# SCH_ReTOoric_2025-10-21.net
KiCad netlist of a schematic drawn in EasyEDA
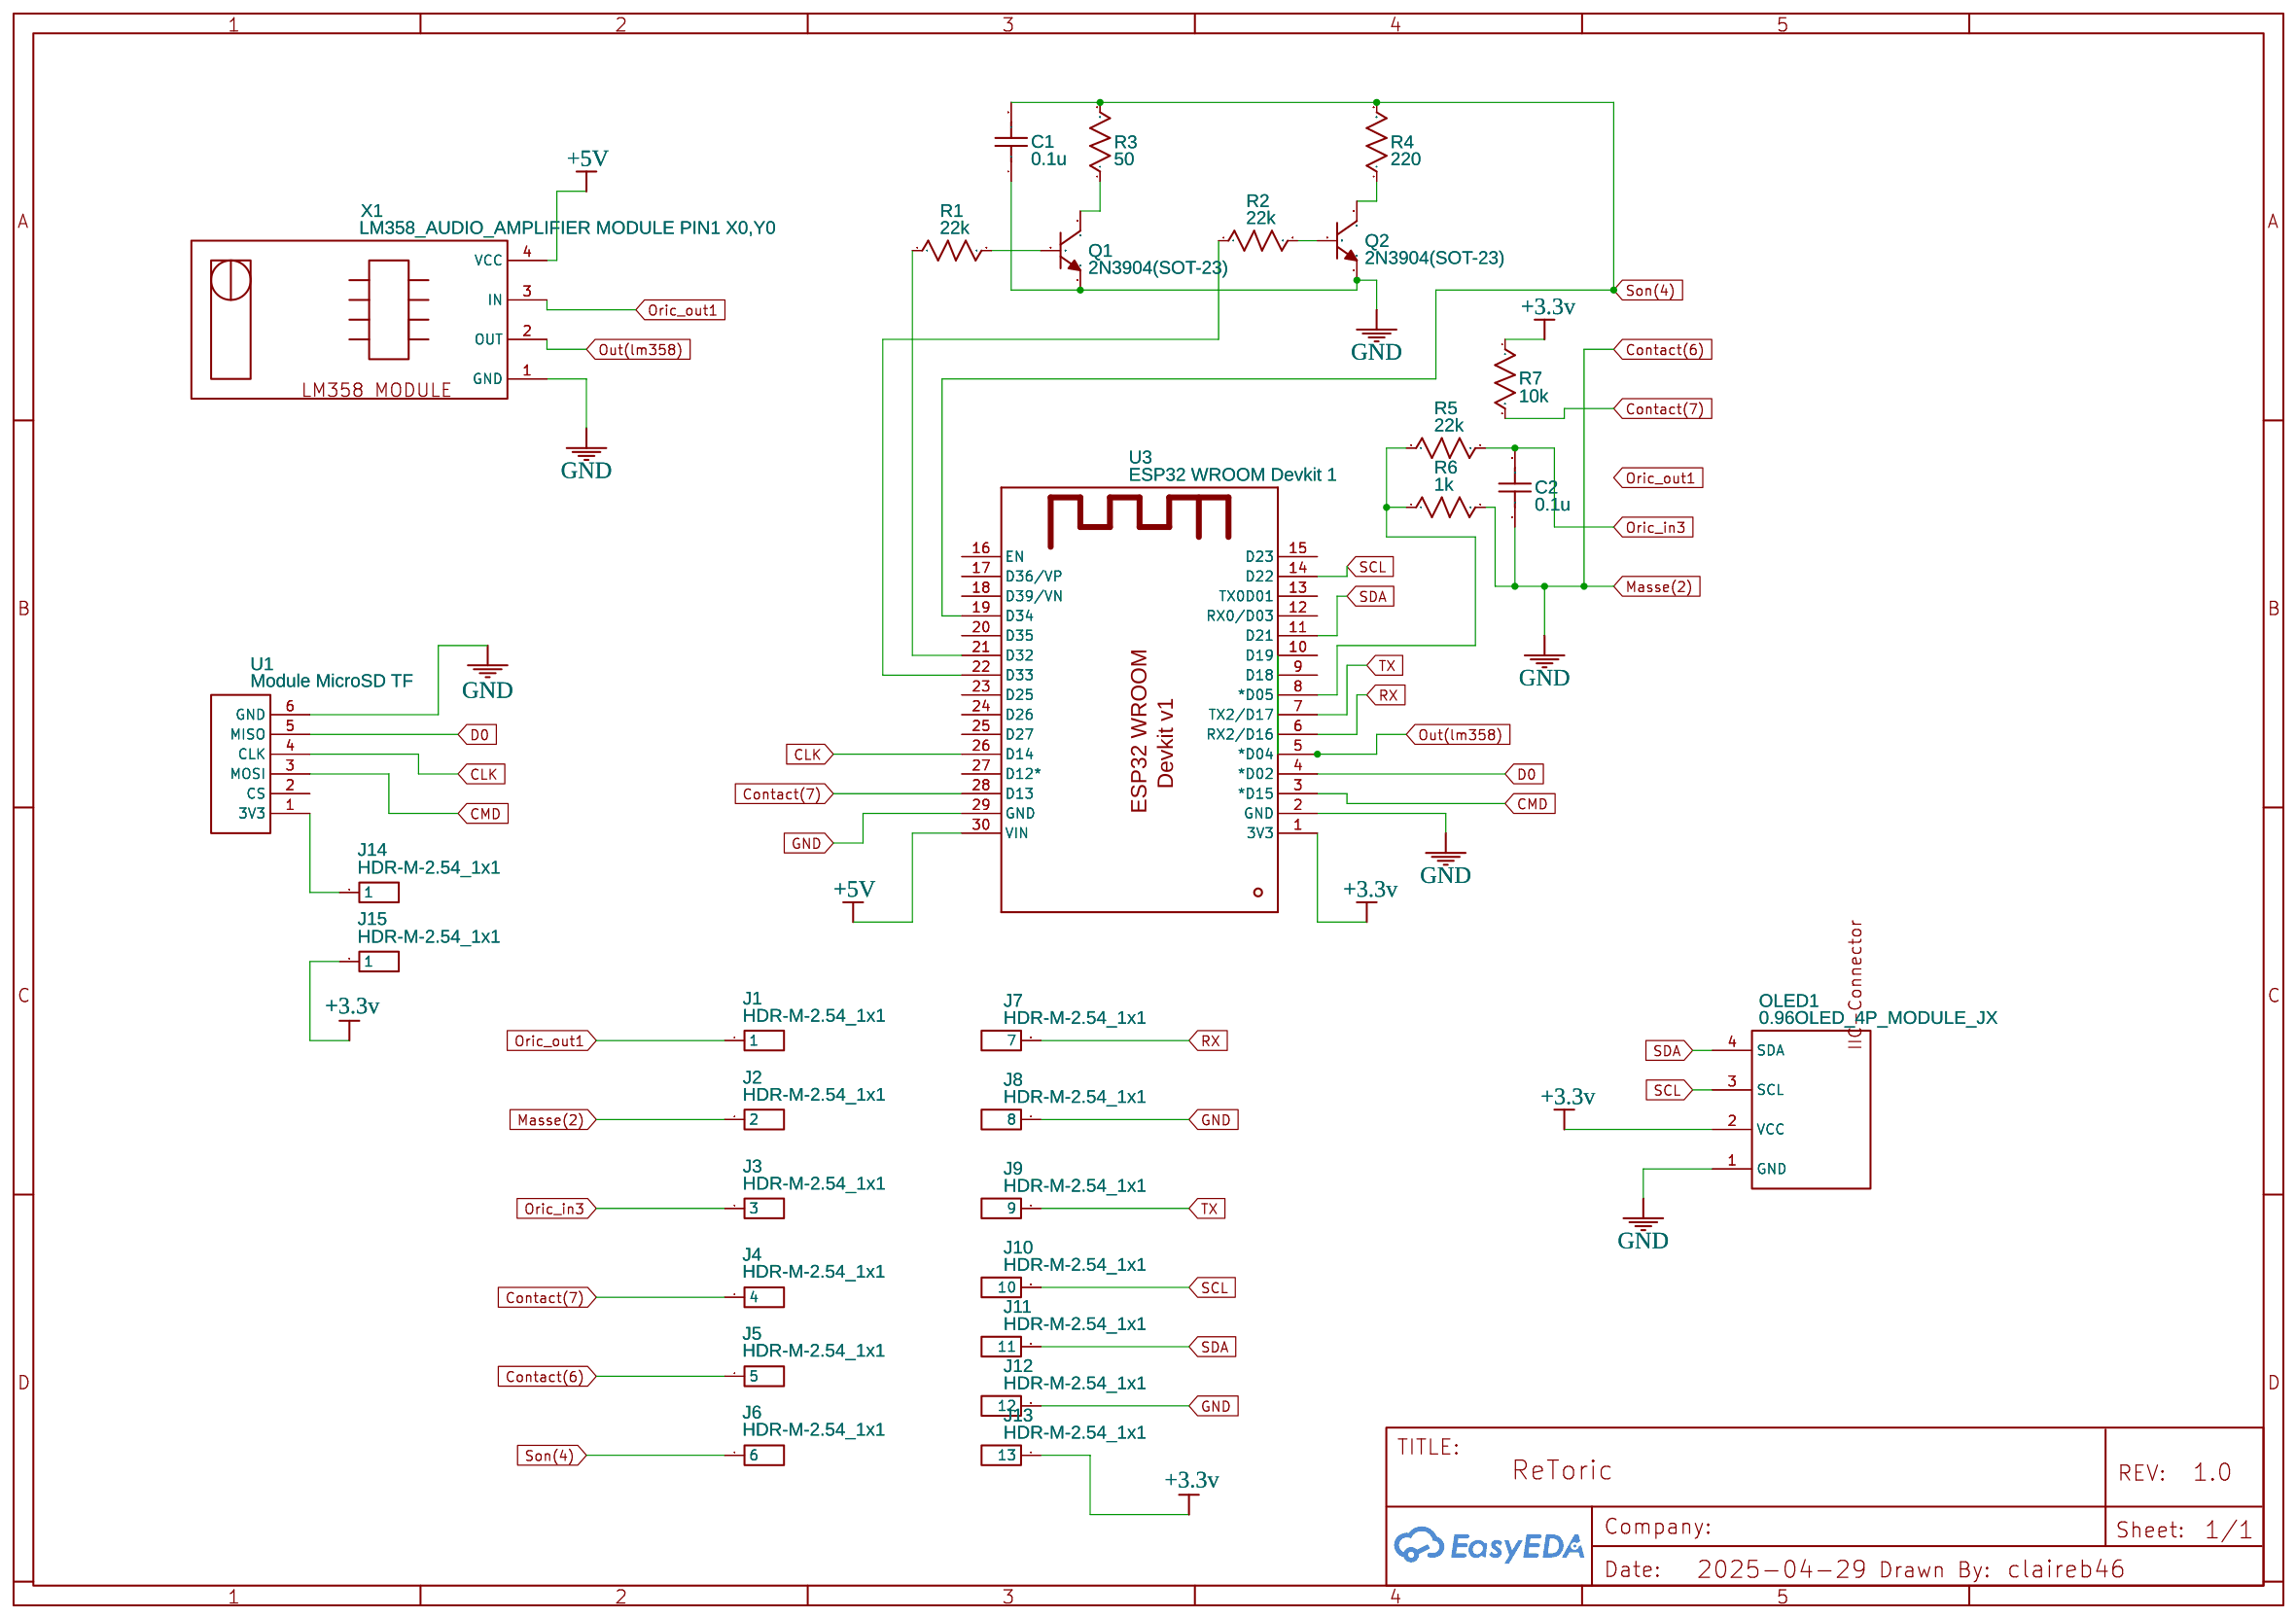
[diagram p0: schematic sheet]

(export (version "E")
  (design (tool "Eeschema 10.0.6"))
  (components
    (comp (ref "C1") (value "0.1u") (libsource (lib "") (part "C_0603_US")))
    (comp (ref "C2") (value "0.1u") (libsource (lib "") (part "C_0603_US")))
    (comp (ref "J1") (value "HDR-M-2.54_1x1") (libsource (lib "") (part "HDR-M-2.54_1x1")))
    (comp (ref "J2") (value "HDR-M-2.54_1x1") (libsource (lib "") (part "HDR-M-2.54_1x1_3")))
    (comp (ref "J3") (value "HDR-M-2.54_1x1") (libsource (lib "") (part "HDR-M-2.54_1x1_2")))
    (comp (ref "J4") (value "HDR-M-2.54_1x1") (libsource (lib "") (part "HDR-M-2.54_1x1_11")))
    (comp (ref "J5") (value "HDR-M-2.54_1x1") (libsource (lib "") (part "HDR-M-2.54_1x1_1")))
    (comp (ref "J6") (value "HDR-M-2.54_1x1") (libsource (lib "") (part "HDR-M-2.54_1x1_7")))
    (comp (ref "J7") (value "HDR-M-2.54_1x1") (libsource (lib "") (part "HDR-M-2.54_1x1_12")))
    (comp (ref "J8") (value "HDR-M-2.54_1x1") (libsource (lib "") (part "HDR-M-2.54_1x1_8")))
    (comp (ref "J9") (value "HDR-M-2.54_1x1") (libsource (lib "") (part "HDR-M-2.54_1x1_9")))
    (comp (ref "J10") (value "HDR-M-2.54_1x1") (libsource (lib "") (part "HDR-M-2.54_1x1_5")))
    (comp (ref "J11") (value "HDR-M-2.54_1x1") (libsource (lib "") (part "HDR-M-2.54_1x1_4")))
    (comp (ref "J12") (value "HDR-M-2.54_1x1") (libsource (lib "") (part "HDR-M-2.54_1x1_10")))
    (comp (ref "J13") (value "HDR-M-2.54_1x1") (libsource (lib "") (part "HDR-M-2.54_1x1_6")))
    (comp (ref "J14") (value "HDR-M-2.54_1x1") (libsource (lib "") (part "HDR-M-2.54_1x1")))
    (comp (ref "J15") (value "HDR-M-2.54_1x1") (libsource (lib "") (part "HDR-M-2.54_1x1")))
    (comp (ref "OLED1") (value "0.96OLED_4P_MODULE_JX") (libsource (lib "") (part "0.96OLED_4P_MODULE_JX")))
    (comp (ref "Q1")
      (value "2N3904(SOT-23)")
      (fields (field (name "Manufacturer Part") "2n3904S-RTK/PS") (field (name "Manufacturer") "KEC"))
      (libsource (lib "") (part "2N3904(SOT-23)"))
    )
    (comp (ref "Q2")
      (value "2N3904(SOT-23)")
      (fields (field (name "Manufacturer Part") "2n3904S-RTK/PS") (field (name "Manufacturer") "KEC"))
      (libsource (lib "") (part "2N3904(SOT-23)"))
    )
    (comp (ref "R1") (value "22k") (libsource (lib "") (part "R_0603_US")))
    (comp (ref "R2") (value "22k") (libsource (lib "") (part "R_0603_US")))
    (comp (ref "R3") (value "50") (libsource (lib "") (part "R_0603_US_2")))
    (comp (ref "R4") (value "220") (libsource (lib "") (part "R_0603_US_2")))
    (comp (ref "R5") (value "22k") (libsource (lib "") (part "R_0603_US")))
    (comp (ref "R6") (value "1k") (libsource (lib "") (part "R_0603_US")))
    (comp (ref "R7") (value "10k") (libsource (lib "") (part "R_0603_US_1")))
    (comp (ref "U1")
      (value "Module MicroSD TF")
      (fields
        (field (name "Manufacturer Part") "TF Micro SD Card Module")
        (field (name "Manufacturer") "SZHAD Technology Store")
      )
      (libsource (lib "") (part "Module MicroSD TF"))
    )
    (comp (ref "U3")
      (value "ESP32 WROOM Devkit 1")
      (fields (field (name "Manufacturer") "Espresssif"))
      (libsource (lib "") (part "ESP32 WROOM Devkit 1"))
    )
    (comp (ref "X1")
      (value "LM358_AUDIO_AMPLIFIER MODULE PIN1 X0,Y0")
      (fields (field (name "Manufacturer Part") "4mm cable to pcb concector 2pins"))
      (libsource (lib "") (part "LM358_AUDIO_AMPLIFIER MODULE PIN1 X0,Y0"))
    )
  )
  (nets
    (net (code "1") (name "+3.3v") (class "Default")
      (node (ref "J13") (pin "1") (pinfunction "13_1") (pintype "input"))
      (node (ref "J15") (pin "1") (pinfunction "1_1") (pintype "input"))
      (node (ref "OLED1") (pin "2") (pinfunction "VCC_2") (pintype "unspecified"))
      (node (ref "R7") (pin "1") (pinfunction "1_1") (pintype "unspecified"))
      (node (ref "U3") (pin "1") (pinfunction "3V3_1") (pintype "passive"))
    )
    (net (code "2") (name "+5V") (class "Default")
      (node (ref "U3") (pin "30") (pinfunction "VIN_30") (pintype "passive"))
      (node (ref "X1") (pin "4") (pinfunction "VCC_4") (pintype "unspecified"))
    )
    (net (code "3") (name "CLK") (class "Default")
      (node (ref "U1") (pin "4") (pinfunction "CLK_4") (pintype "unspecified"))
      (node (ref "U3") (pin "26") (pinfunction "D14_26") (pintype "bidirectional"))
    )
    (net (code "4") (name "CMD") (class "Default")
      (node (ref "U1") (pin "3") (pinfunction "MOSI_3") (pintype "unspecified"))
      (node (ref "U3") (pin "3") (pinfunction "*D15_3") (pintype "bidirectional"))
    )
    (net (code "5") (name "Contact(6)") (class "Default")
      (node (ref "C1") (pin "1") (pinfunction "1_1") (pintype "unspecified"))
      (node (ref "C2") (pin "1") (pinfunction "1_1") (pintype "unspecified"))
      (node (ref "J12") (pin "1") (pinfunction "12_1") (pintype "input"))
      (node (ref "J2") (pin "1") (pinfunction "2_1") (pintype "input"))
      (node (ref "J5") (pin "1") (pinfunction "5_1") (pintype "input"))
      (node (ref "J8") (pin "1") (pinfunction "8_1") (pintype "input"))
      (node (ref "OLED1") (pin "1") (pinfunction "GND_1") (pintype "unspecified"))
      (node (ref "Q1") (pin "1") (pinfunction "E_1") (pintype "input"))
      (node (ref "Q2") (pin "1") (pinfunction "E_1") (pintype "input"))
      (node (ref "R6") (pin "2") (pinfunction "2_2") (pintype "unspecified"))
      (node (ref "U1") (pin "6") (pinfunction "GND_6") (pintype "unspecified"))
      (node (ref "U3") (pin "2") (pinfunction "GND_2") (pintype "passive"))
      (node (ref "U3") (pin "29") (pinfunction "GND_29") (pintype "passive"))
      (node (ref "X1") (pin "1") (pinfunction "GND_1") (pintype "unspecified"))
    )
    (net (code "6") (name "Contact(7)") (class "Default")
      (node (ref "J4") (pin "1") (pinfunction "4_1") (pintype "input"))
      (node (ref "R7") (pin "2") (pinfunction "2_2") (pintype "unspecified"))
      (node (ref "U3") (pin "28") (pinfunction "D13_28") (pintype "bidirectional"))
    )
    (net (code "7") (name "D0") (class "Default")
      (node (ref "U1") (pin "5") (pinfunction "MISO_5") (pintype "unspecified"))
      (node (ref "U3") (pin "4") (pinfunction "*D02_4") (pintype "bidirectional"))
    )
    (net (code "8") (name "Net-(Q1-B)") (class "Default")
      (node (ref "Q1") (pin "2") (pinfunction "B_2") (pintype "input"))
      (node (ref "R1") (pin "2") (pinfunction "2_2") (pintype "unspecified"))
    )
    (net (code "9") (name "Net-(Q1-C)") (class "Default")
      (node (ref "Q1") (pin "3") (pinfunction "C_3") (pintype "input"))
      (node (ref "R3") (pin "1") (pinfunction "1_1") (pintype "unspecified"))
    )
    (net (code "10") (name "Net-(Q2-B)") (class "Default")
      (node (ref "Q2") (pin "2") (pinfunction "B_2") (pintype "input"))
      (node (ref "R2") (pin "2") (pinfunction "2_2") (pintype "unspecified"))
    )
    (net (code "11") (name "Net-(Q2-C)") (class "Default")
      (node (ref "Q2") (pin "3") (pinfunction "C_3") (pintype "input"))
      (node (ref "R4") (pin "1") (pinfunction "1_1") (pintype "unspecified"))
    )
    (net (code "12") (name "Net-(U1-3V3)") (class "Default")
      (node (ref "J14") (pin "1") (pinfunction "1_1") (pintype "input"))
      (node (ref "U1") (pin "1") (pinfunction "3V3_1") (pintype "unspecified"))
    )
    (net (code "13") (name "Net-(U3-*D05)") (class "Default")
      (node (ref "R5") (pin "1") (pinfunction "1_1") (pintype "unspecified"))
      (node (ref "R6") (pin "1") (pinfunction "1_1") (pintype "unspecified"))
      (node (ref "U3") (pin "8") (pinfunction "*D05_8") (pintype "bidirectional"))
    )
    (net (code "14") (name "Net-(U3-D32)") (class "Default")
      (node (ref "R1") (pin "1") (pinfunction "1_1") (pintype "unspecified"))
      (node (ref "U3") (pin "21") (pinfunction "D32_21") (pintype "bidirectional"))
    )
    (net (code "15") (name "Net-(U3-D33)") (class "Default")
      (node (ref "R2") (pin "1") (pinfunction "1_1") (pintype "unspecified"))
      (node (ref "U3") (pin "22") (pinfunction "D33_22") (pintype "bidirectional"))
    )
    (net (code "16") (name "Oric_in3") (class "Default")
      (node (ref "C2") (pin "2") (pinfunction "2_2") (pintype "unspecified"))
      (node (ref "J3") (pin "1") (pinfunction "3_1") (pintype "input"))
      (node (ref "R5") (pin "2") (pinfunction "2_2") (pintype "unspecified"))
    )
    (net (code "17") (name "Oric_out1") (class "Default")
      (node (ref "J1") (pin "1") (pinfunction "1_1") (pintype "input"))
      (node (ref "X1") (pin "3") (pinfunction "IN_3") (pintype "unspecified"))
    )
    (net (code "18") (name "Out(lm358)") (class "Default")
      (node (ref "U3") (pin "5") (pinfunction "*D04_5") (pintype "bidirectional"))
      (node (ref "X1") (pin "2") (pinfunction "OUT_2") (pintype "unspecified"))
    )
    (net (code "19") (name "RX") (class "Default")
      (node (ref "J7") (pin "1") (pinfunction "7_1") (pintype "input"))
      (node (ref "U3") (pin "6") (pinfunction "RX2/D16_6") (pintype "bidirectional"))
    )
    (net (code "20") (name "SCL") (class "Default")
      (node (ref "J10") (pin "1") (pinfunction "10_1") (pintype "input"))
      (node (ref "OLED1") (pin "3") (pinfunction "SCL_3") (pintype "unspecified"))
      (node (ref "U3") (pin "14") (pinfunction "D22_14") (pintype "bidirectional"))
    )
    (net (code "21") (name "SDA") (class "Default")
      (node (ref "J11") (pin "1") (pinfunction "11_1") (pintype "input"))
      (node (ref "OLED1") (pin "4") (pinfunction "SDA_4") (pintype "unspecified"))
      (node (ref "U3") (pin "11") (pinfunction "D21_11") (pintype "bidirectional"))
    )
    (net (code "22") (name "Son(4)") (class "Default")
      (node (ref "C1") (pin "2") (pinfunction "2_2") (pintype "unspecified"))
      (node (ref "J6") (pin "1") (pinfunction "6_1") (pintype "input"))
      (node (ref "R3") (pin "2") (pinfunction "2_2") (pintype "unspecified"))
      (node (ref "R4") (pin "2") (pinfunction "2_2") (pintype "unspecified"))
      (node (ref "U3") (pin "19") (pinfunction "D34_19") (pintype "input"))
    )
    (net (code "23") (name "TX") (class "Default")
      (node (ref "J9") (pin "1") (pinfunction "9_1") (pintype "input"))
      (node (ref "U3") (pin "7") (pinfunction "TX2/D17_7") (pintype "bidirectional"))
    )
    (net (code "24") (name "unconnected-(U1-CS-Pad2)") (class "Default")
      (node (ref "U1") (pin "2") (pinfunction "CS_2") (pintype "unspecified"))
    )
    (net (code "25") (name "unconnected-(U3-D12*-Pad27)") (class "Default")
      (node (ref "U3") (pin "27") (pinfunction "D12*_27") (pintype "bidirectional"))
    )
    (net (code "26") (name "unconnected-(U3-D18-Pad9)") (class "Default")
      (node (ref "U3") (pin "9") (pinfunction "D18_9") (pintype "bidirectional"))
    )
    (net (code "27") (name "unconnected-(U3-D19-Pad10)") (class "Default")
      (node (ref "U3") (pin "10") (pinfunction "D19_10") (pintype "bidirectional"))
    )
    (net (code "28") (name "unconnected-(U3-D23-Pad15)") (class "Default")
      (node (ref "U3") (pin "15") (pinfunction "D23_15") (pintype "bidirectional"))
    )
    (net (code "29") (name "unconnected-(U3-D25-Pad23)") (class "Default")
      (node (ref "U3") (pin "23") (pinfunction "D25_23") (pintype "bidirectional"))
    )
    (net (code "30") (name "unconnected-(U3-D26-Pad24)") (class "Default")
      (node (ref "U3") (pin "24") (pinfunction "D26_24") (pintype "bidirectional"))
    )
    (net (code "31") (name "unconnected-(U3-D27-Pad25)") (class "Default")
      (node (ref "U3") (pin "25") (pinfunction "D27_25") (pintype "bidirectional"))
    )
    (net (code "32") (name "unconnected-(U3-D35-Pad20)") (class "Default")
      (node (ref "U3") (pin "20") (pinfunction "D35_20") (pintype "input"))
    )
    (net (code "33") (name "unconnected-(U3-D36{slash}VP-Pad17)") (class "Default")
      (node (ref "U3") (pin "17") (pinfunction "D36/VP_17") (pintype "input"))
    )
    (net (code "34") (name "unconnected-(U3-D39{slash}VN-Pad18)") (class "Default")
      (node (ref "U3") (pin "18") (pinfunction "D39/VN_18") (pintype "input"))
    )
    (net (code "35") (name "unconnected-(U3-EN-Pad16)") (class "Default")
      (node (ref "U3") (pin "16") (pinfunction "EN_16") (pintype "bidirectional"))
    )
    (net (code "36") (name "unconnected-(U3-RX0{slash}D03-Pad12)") (class "Default")
      (node (ref "U3") (pin "12") (pinfunction "RX0/D03_12") (pintype "bidirectional"))
    )
    (net (code "37") (name "unconnected-(U3-TX0D01-Pad13)") (class "Default")
      (node (ref "U3") (pin "13") (pinfunction "TX0D01_13") (pintype "bidirectional"))
    )
  )
)
